# IHM.net
KiCad netlist of a schematic drawn in Altium Designer
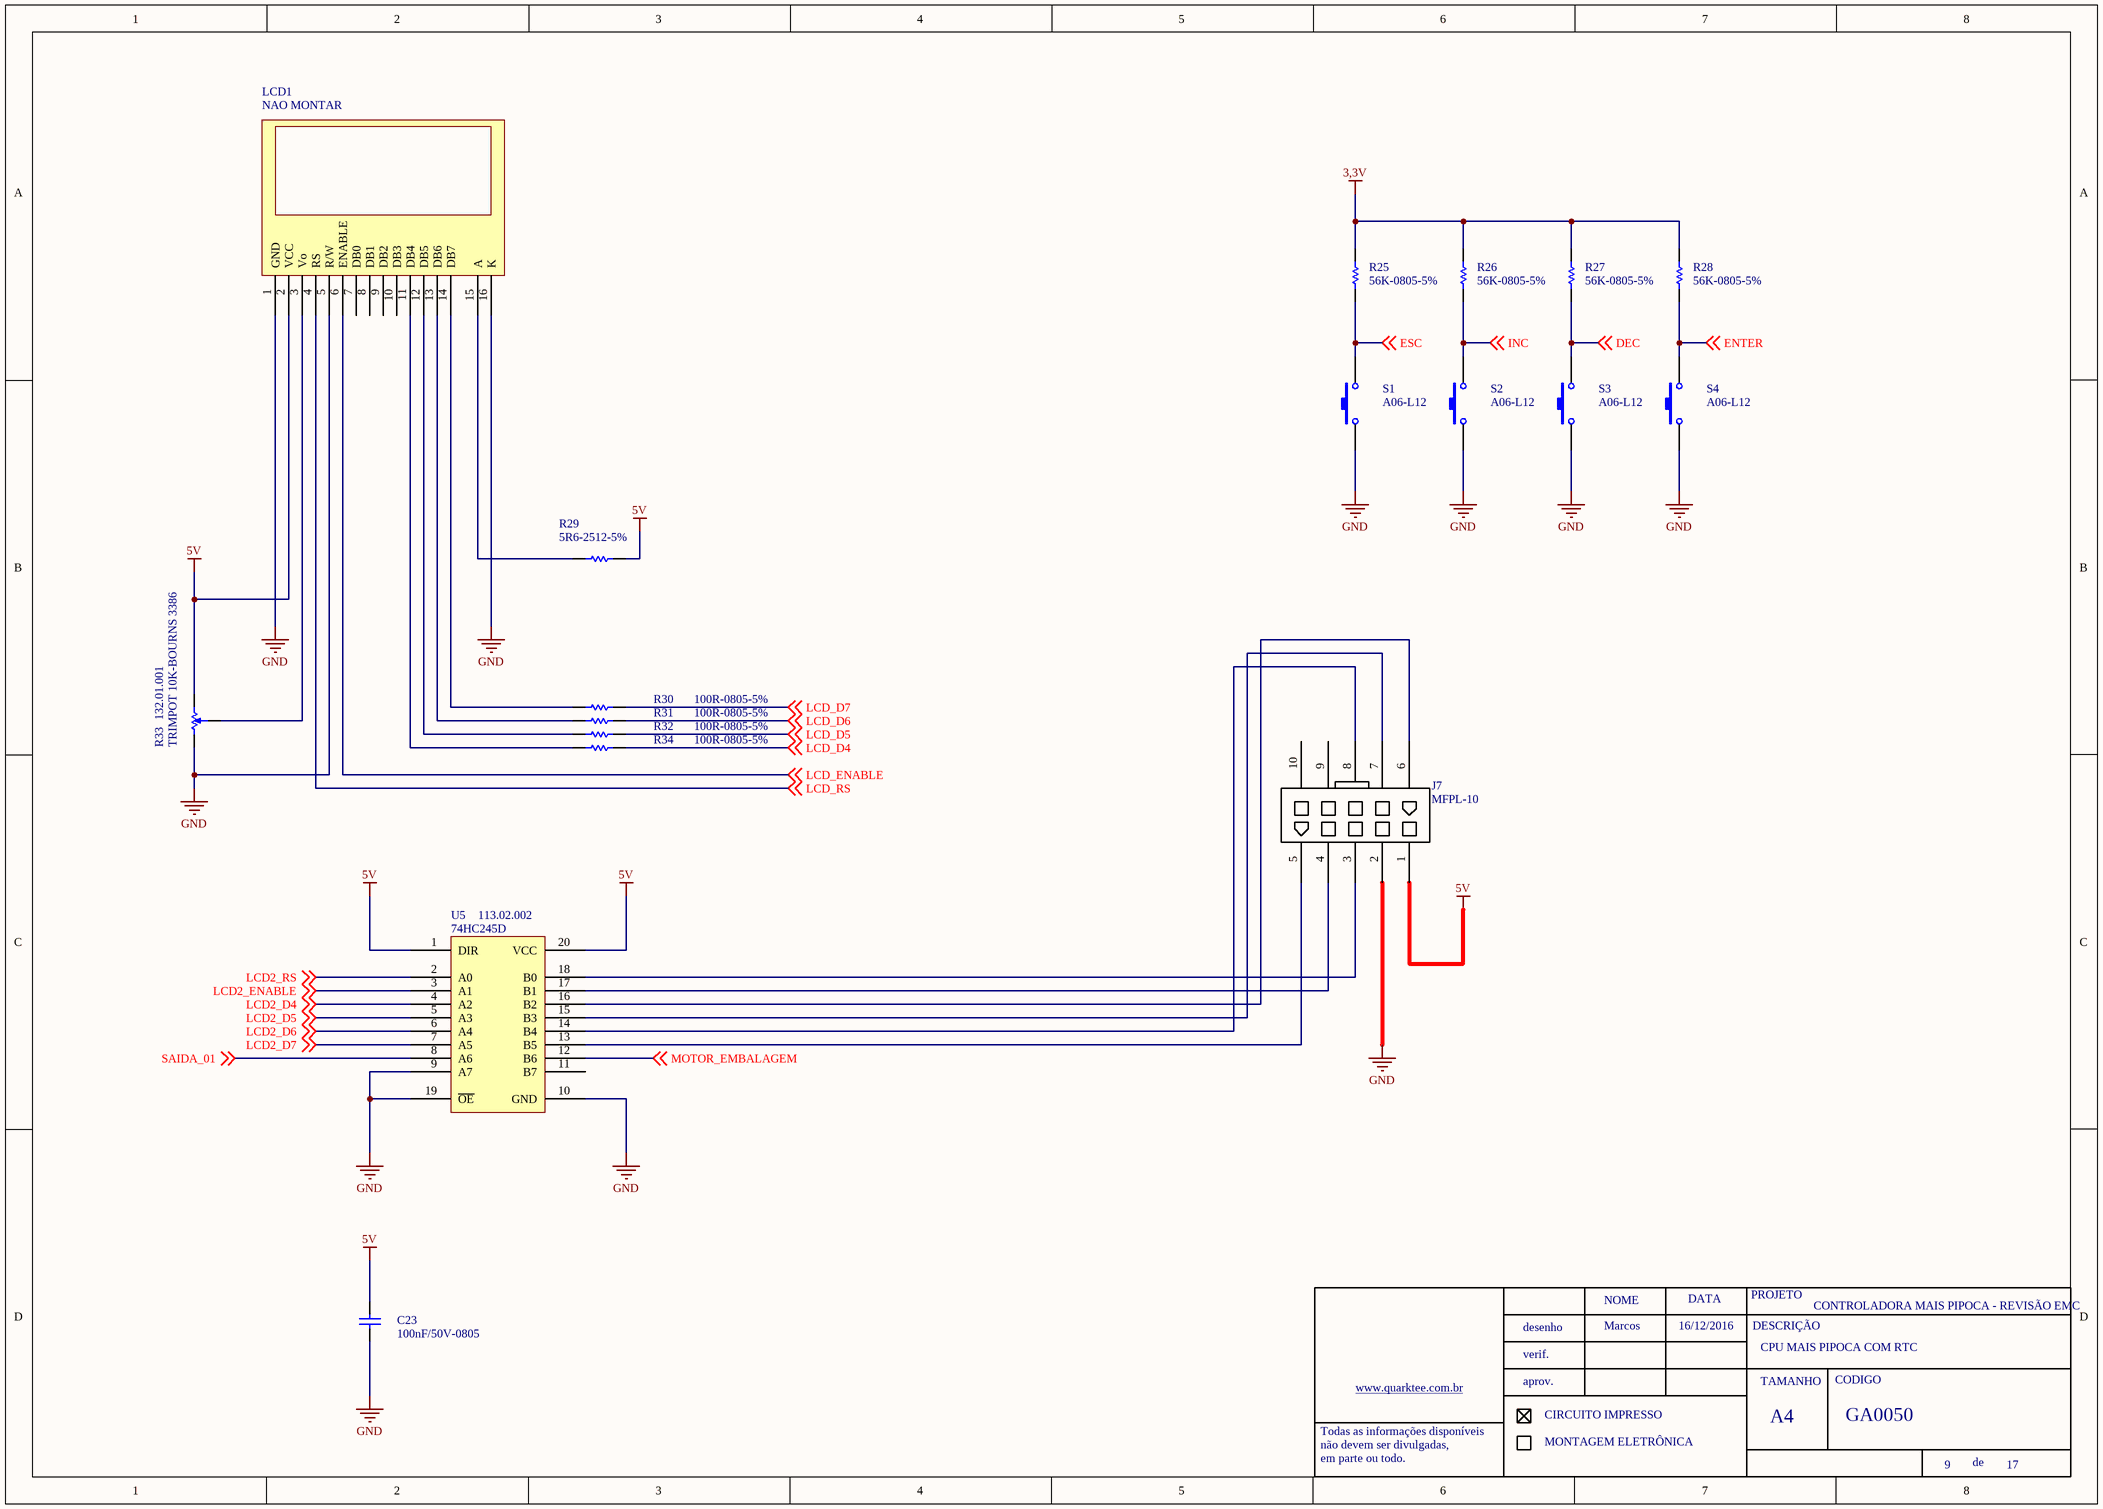
[diagram p0: IHM.SchDoc]

(export (version "E")
  (design (tool "Eeschema 10.0.6"))
  (components
    (comp (ref "C23")
      (value "100nF/50V-0805")
      (footprint "0805-REVISADO ONDA")
      (description "100nF/50-0805-NPO")
      (libsource (lib "AquinoLib") (part "100nF/50-0805-NPO"))
    )
    (comp (ref "J7") (value "MFPL-10") (libsource (lib "AquinoLib") (part "MFPL-10")))
    (comp (ref "LCD1")
      (value "NAO MONTAR")
      (footprint "WH1602B_DS")
      (description "WH1602A")
      (libsource (lib "ChaveDigital3") (part "WH1602A"))
    )
    (comp (ref "R25")
      (value "56K-0805-5%")
      (footprint "0805-REVISADO ONDA")
      (libsource (lib "AquinoLib") (part "56K-0805-5%"))
    )
    (comp (ref "R26")
      (value "56K-0805-5%")
      (footprint "0805-REVISADO ONDA")
      (libsource (lib "AquinoLib") (part "56K-0805-5%"))
    )
    (comp (ref "R27")
      (value "56K-0805-5%")
      (footprint "0805-REVISADO ONDA")
      (libsource (lib "AquinoLib") (part "56K-0805-5%"))
    )
    (comp (ref "R28")
      (value "56K-0805-5%")
      (footprint "0805-REVISADO ONDA")
      (libsource (lib "AquinoLib") (part "56K-0805-5%"))
    )
    (comp (ref "R29")
      (value "5R6-2512-5%")
      (footprint "2512 - REVISADO ONDA")
      (description "5R6-CR100")
      (libsource (lib "ChaveDigital3") (part "RES 5R6-CR100"))
    )
    (comp (ref "R30")
      (value "100R-0805-5%")
      (footprint "0805-REVISADO ONDA")
      (libsource (lib "AquinoLib") (part "100R-0805-5%"))
    )
    (comp (ref "R31")
      (value "100R-0805-5%")
      (footprint "0805-REVISADO ONDA")
      (libsource (lib "AquinoLib") (part "100R-0805-5%"))
    )
    (comp (ref "R32")
      (value "100R-0805-5%")
      (footprint "0805-REVISADO ONDA")
      (libsource (lib "AquinoLib") (part "100R-0805-5%"))
    )
    (comp (ref "R33")
      (value "TRIMPOT 10K-BOURNS 3386")
      (footprint "TRIMPOT 3386")
      (fields (field (name "ERP") "132.01.001"))
      (libsource (lib "ChaveDigital3") (part "TRIMPOT 3386 50K"))
    )
    (comp (ref "R34")
      (value "100R-0805-5%")
      (footprint "0805-REVISADO ONDA")
      (libsource (lib "AquinoLib") (part "100R-0805-5%"))
    )
    (comp (ref "S1")
      (value "A06-L12")
      (footprint "CHAVE_A06")
      (libsource (lib "ChaveDigital3") (part "A06-L12"))
    )
    (comp (ref "S2")
      (value "A06-L12")
      (footprint "CHAVE_A06")
      (libsource (lib "ChaveDigital3") (part "A06-L12"))
    )
    (comp (ref "S3")
      (value "A06-L12")
      (footprint "CHAVE_A06")
      (libsource (lib "ChaveDigital3") (part "A06-L12"))
    )
    (comp (ref "S4")
      (value "A06-L12")
      (footprint "CHAVE_A06")
      (libsource (lib "ChaveDigital3") (part "A06-L12"))
    )
    (comp (ref "U5")
      (value "74HC245D")
      (footprint "SOIC-20")
      (fields (field (name "ERP") "113.02.002"))
      (libsource (lib "ChaveDigital3") (part "74HC245D"))
    )
  )
  (nets
    (net (code "1") (name "3,3V") (class "Default")
      (node (ref "R25") (pin "1") (pinfunction "1_1") (pintype "passive"))
      (node (ref "R26") (pin "1") (pinfunction "1_1") (pintype "passive"))
      (node (ref "R27") (pin "1") (pinfunction "1_1") (pintype "passive"))
      (node (ref "R28") (pin "1") (pinfunction "1_1") (pintype "passive"))
    )
    (net (code "2") (name "5V") (class "Default")
      (node (ref "C23") (pin "2") (pinfunction "2_2") (pintype "passive"))
      (node (ref "J7") (pin "1") (pinfunction "1_1") (pintype "passive"))
      (node (ref "LCD1") (pin "2") (pinfunction "VCC_2") (pintype "passive"))
      (node (ref "R29") (pin "1") (pinfunction "1_1") (pintype "passive"))
      (node (ref "R33") (pin "1") (pinfunction "1_1") (pintype "passive"))
      (node (ref "U5") (pin "1") (pinfunction "DIR_1") (pintype "passive"))
      (node (ref "U5") (pin "20") (pinfunction "VCC_20") (pintype "passive"))
    )
    (net (code "3") (name "DEC") (class "Default")
      (node (ref "R27") (pin "2") (pinfunction "2_2") (pintype "passive"))
      (node (ref "S3") (pin "2") (pinfunction "2_2") (pintype "passive"))
    )
    (net (code "4") (name "ENTER") (class "Default")
      (node (ref "R28") (pin "2") (pinfunction "2_2") (pintype "passive"))
      (node (ref "S4") (pin "2") (pinfunction "2_2") (pintype "passive"))
    )
    (net (code "5") (name "ESC") (class "Default")
      (node (ref "R25") (pin "2") (pinfunction "2_2") (pintype "passive"))
      (node (ref "S1") (pin "2") (pinfunction "2_2") (pintype "passive"))
    )
    (net (code "6") (name "GND") (class "Default")
      (node (ref "C23") (pin "1") (pinfunction "1_1") (pintype "passive"))
      (node (ref "J7") (pin "2") (pinfunction "2_2") (pintype "passive"))
      (node (ref "LCD1") (pin "1") (pinfunction "GND_1") (pintype "passive"))
      (node (ref "LCD1") (pin "16") (pinfunction "K_16") (pintype "passive"))
      (node (ref "LCD1") (pin "5") (pinfunction "R/W_5") (pintype "passive"))
      (node (ref "R33") (pin "3") (pinfunction "3_3") (pintype "passive"))
      (node (ref "S1") (pin "1") (pinfunction "1_1") (pintype "passive"))
      (node (ref "S2") (pin "1") (pinfunction "1_1") (pintype "passive"))
      (node (ref "S3") (pin "1") (pinfunction "1_1") (pintype "passive"))
      (node (ref "S4") (pin "1") (pinfunction "1_1") (pintype "passive"))
      (node (ref "U5") (pin "10") (pinfunction "GND_10") (pintype "passive"))
      (node (ref "U5") (pin "19") (pinfunction "~{OE}_19") (pintype "passive"))
      (node (ref "U5") (pin "9") (pinfunction "A7_9") (pintype "passive"))
    )
    (net (code "7") (name "INC") (class "Default")
      (node (ref "R26") (pin "2") (pinfunction "2_2") (pintype "passive"))
      (node (ref "S2") (pin "2") (pinfunction "2_2") (pintype "passive"))
    )
    (net (code "8") (name "LCD2_D4") (class "Default")
      (node (ref "U5") (pin "4") (pinfunction "A2_4") (pintype "passive"))
    )
    (net (code "9") (name "LCD2_D5") (class "Default")
      (node (ref "U5") (pin "5") (pinfunction "A3_5") (pintype "passive"))
    )
    (net (code "10") (name "LCD2_D6") (class "Default")
      (node (ref "U5") (pin "6") (pinfunction "A4_6") (pintype "passive"))
    )
    (net (code "11") (name "LCD2_D7") (class "Default")
      (node (ref "U5") (pin "7") (pinfunction "A5_7") (pintype "passive"))
    )
    (net (code "12") (name "LCD2_ENABLE") (class "Default")
      (node (ref "U5") (pin "3") (pinfunction "A1_3") (pintype "passive"))
    )
    (net (code "13") (name "LCD2_RS") (class "Default")
      (node (ref "U5") (pin "2") (pinfunction "A0_2") (pintype "passive"))
    )
    (net (code "14") (name "LCD_D4") (class "Default")
      (node (ref "R34") (pin "2") (pinfunction "2_2") (pintype "passive"))
    )
    (net (code "15") (name "LCD_D5") (class "Default")
      (node (ref "R32") (pin "2") (pinfunction "2_2") (pintype "passive"))
    )
    (net (code "16") (name "LCD_D6") (class "Default")
      (node (ref "R31") (pin "2") (pinfunction "2_2") (pintype "passive"))
    )
    (net (code "17") (name "LCD_D7") (class "Default")
      (node (ref "R30") (pin "2") (pinfunction "2_2") (pintype "passive"))
    )
    (net (code "18") (name "LCD_ENABLE") (class "Default")
      (node (ref "LCD1") (pin "6") (pinfunction "ENABLE_6") (pintype "passive"))
    )
    (net (code "19") (name "LCD_RS") (class "Default")
      (node (ref "LCD1") (pin "4") (pinfunction "RS_4") (pintype "passive"))
    )
    (net (code "20") (name "MOTOR_EMBALAGEM") (class "Default")
      (node (ref "U5") (pin "12") (pinfunction "B6_12") (pintype "passive"))
    )
    (net (code "21") (name "Net-(LCD1-A)") (class "Default")
      (node (ref "LCD1") (pin "15") (pinfunction "A_15") (pintype "passive"))
      (node (ref "R29") (pin "2") (pinfunction "2_2") (pintype "passive"))
    )
    (net (code "22") (name "Net-(LCD1-DB4)") (class "Default")
      (node (ref "LCD1") (pin "11") (pinfunction "DB4_11") (pintype "passive"))
      (node (ref "R34") (pin "1") (pinfunction "1_1") (pintype "passive"))
    )
    (net (code "23") (name "Net-(LCD1-DB5)") (class "Default")
      (node (ref "LCD1") (pin "12") (pinfunction "DB5_12") (pintype "passive"))
      (node (ref "R32") (pin "1") (pinfunction "1_1") (pintype "passive"))
    )
    (net (code "24") (name "Net-(LCD1-DB6)") (class "Default")
      (node (ref "LCD1") (pin "13") (pinfunction "DB6_13") (pintype "passive"))
      (node (ref "R31") (pin "1") (pinfunction "1_1") (pintype "passive"))
    )
    (net (code "25") (name "Net-(LCD1-DB7)") (class "Default")
      (node (ref "LCD1") (pin "14") (pinfunction "DB7_14") (pintype "passive"))
      (node (ref "R30") (pin "1") (pinfunction "1_1") (pintype "passive"))
    )
    (net (code "26") (name "Net-(LCD1-Vo)") (class "Default")
      (node (ref "LCD1") (pin "3") (pinfunction "Vo_3") (pintype "passive"))
      (node (ref "R33") (pin "2") (pinfunction "2_2") (pintype "passive"))
    )
    (net (code "27") (name "Net-(U5-B0)") (class "Default")
      (node (ref "J7") (pin "3") (pinfunction "3_3") (pintype "passive"))
      (node (ref "U5") (pin "18") (pinfunction "B0_18") (pintype "passive"))
    )
    (net (code "28") (name "Net-(U5-B1)") (class "Default")
      (node (ref "J7") (pin "4") (pinfunction "4_4") (pintype "passive"))
      (node (ref "U5") (pin "17") (pinfunction "B1_17") (pintype "passive"))
    )
    (net (code "29") (name "Net-(U5-B2)") (class "Default")
      (node (ref "J7") (pin "6") (pinfunction "6_6") (pintype "passive"))
      (node (ref "U5") (pin "16") (pinfunction "B2_16") (pintype "passive"))
    )
    (net (code "30") (name "Net-(U5-B3)") (class "Default")
      (node (ref "J7") (pin "7") (pinfunction "7_7") (pintype "passive"))
      (node (ref "U5") (pin "15") (pinfunction "B3_15") (pintype "passive"))
    )
    (net (code "31") (name "Net-(U5-B4)") (class "Default")
      (node (ref "J7") (pin "8") (pinfunction "8_8") (pintype "passive"))
      (node (ref "U5") (pin "14") (pinfunction "B4_14") (pintype "passive"))
    )
    (net (code "32") (name "Net-(U5-B5)") (class "Default")
      (node (ref "J7") (pin "5") (pinfunction "5_5") (pintype "passive"))
      (node (ref "U5") (pin "13") (pinfunction "B5_13") (pintype "passive"))
    )
    (net (code "33") (name "SAIDA_01") (class "Default")
      (node (ref "U5") (pin "8") (pinfunction "A6_8") (pintype "passive"))
    )
    (net (code "34") (name "unconnected-(J7-Pad9)") (class "Default")
      (node (ref "J7") (pin "9") (pinfunction "9_9") (pintype "passive"))
    )
    (net (code "35") (name "unconnected-(J7-Pad10)") (class "Default")
      (node (ref "J7") (pin "10") (pinfunction "10_10") (pintype "passive"))
    )
    (net (code "36") (name "unconnected-(LCD1-DB0-Pad7)") (class "Default")
      (node (ref "LCD1") (pin "7") (pinfunction "DB0_7") (pintype "passive"))
    )
    (net (code "37") (name "unconnected-(LCD1-DB1-Pad8)") (class "Default")
      (node (ref "LCD1") (pin "8") (pinfunction "DB1_8") (pintype "passive"))
    )
    (net (code "38") (name "unconnected-(LCD1-DB2-Pad9)") (class "Default")
      (node (ref "LCD1") (pin "9") (pinfunction "DB2_9") (pintype "passive"))
    )
    (net (code "39") (name "unconnected-(LCD1-DB3-Pad10)") (class "Default")
      (node (ref "LCD1") (pin "10") (pinfunction "DB3_10") (pintype "passive"))
    )
    (net (code "40") (name "unconnected-(U5-B7-Pad11)") (class "Default")
      (node (ref "U5") (pin "11") (pinfunction "B7_11") (pintype "passive"))
    )
  )
)
